# transistor.net
KiCad netlist of a schematic drawn in EAGLE
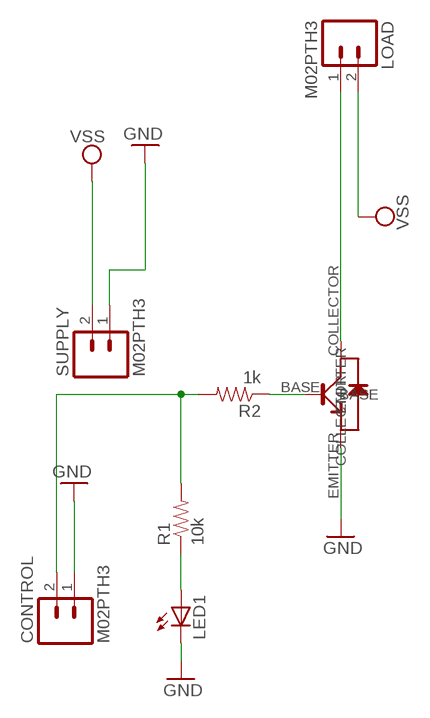
[diagram p0: schematic, sheet 1]

(export (version "E")
  (design (tool "Eeschema 10.0.6"))
  (components
    (comp (ref "CONTROL")
      (value "M02PTH3")
      (footprint "eagle-import:1X02_LONGPADS")
      (libsource (lib "eagle-import") (part "M02PTH3"))
    )
    (comp (ref "LED1")
      (value "LEDCHIPLED_0603")
      (footprint "eagle-import:CHIPLED_0603")
      (libsource (lib "eagle-import") (part "LEDCHIPLED_0603"))
    )
    (comp (ref "LOAD")
      (value "M02PTH3")
      (footprint "eagle-import:1X02_LONGPADS")
      (libsource (lib "eagle-import") (part "M02PTH3"))
    )
    (comp (ref "R1")
      (value "10k")
      (footprint "eagle-import:0603-RES")
      (libsource (lib "eagle-import") (part "RESISTOR0603-RES"))
    )
    (comp (ref "R2")
      (value "1k")
      (footprint "eagle-import:0603-RES")
      (libsource (lib "eagle-import") (part "RESISTOR0603-RES"))
    )
    (comp (ref "SUPPLY")
      (value "M02PTH3")
      (footprint "eagle-import:1X02_LONGPADS")
      (libsource (lib "eagle-import") (part "M02PTH3"))
    )
    (comp (ref "U$1")
      (value "STB13007DT4")
      (footprint "eagle-import:D2PAK-TO263")
      (libsource (lib "eagle-import") (part "STB13007DT4"))
    )
  )
  (nets
    (net (code "1") (name "GND") (class "Default")
      (node (ref "CONTROL") (pin "1") (pinfunction "1_1") (pintype "passive"))
      (node (ref "LED1") (pin "C") (pinfunction "C_C") (pintype "passive"))
      (node (ref "SUPPLY") (pin "1") (pinfunction "1_1") (pintype "passive"))
      (node (ref "U$1") (pin "EMITTER") (pinfunction "EMITTER_EMITTER") (pintype "bidirectional"))
    )
    (net (code "2") (name "Net-(CONTROL-Pad2)") (class "Default")
      (node (ref "CONTROL") (pin "2") (pinfunction "2_2") (pintype "passive"))
      (node (ref "R1") (pin "2") (pinfunction "2_2") (pintype "passive"))
      (node (ref "R2") (pin "2") (pinfunction "2_2") (pintype "passive"))
    )
    (net (code "3") (name "Net-(LED1-PadA)") (class "Default")
      (node (ref "LED1") (pin "A") (pinfunction "A_A") (pintype "passive"))
      (node (ref "R1") (pin "1") (pinfunction "1_1") (pintype "passive"))
    )
    (net (code "4") (name "Net-(LOAD-Pad1)") (class "Default")
      (node (ref "LOAD") (pin "1") (pinfunction "1_1") (pintype "passive"))
      (node (ref "U$1") (pin "COLLECTOR") (pinfunction "COLLECTOR_COLLECTOR") (pintype "bidirectional"))
    )
    (net (code "5") (name "Net-(R2-Pad1)") (class "Default")
      (node (ref "R2") (pin "1") (pinfunction "1_1") (pintype "passive"))
      (node (ref "U$1") (pin "BASE") (pinfunction "BASE_BASE") (pintype "bidirectional"))
    )
    (net (code "6") (name "VSS") (class "Default")
      (node (ref "LOAD") (pin "2") (pinfunction "2_2") (pintype "passive"))
      (node (ref "SUPPLY") (pin "2") (pinfunction "2_2") (pintype "passive"))
    )
  )
)
